# iqrfsim.net
KiCad netlist of a schematic drawn in EAGLE
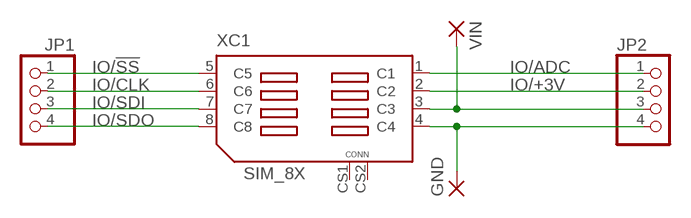
[diagram p0: schematic, sheet 1]

(export (version "E")
  (design (tool "Eeschema 10.0.6"))
  (components
    (comp (ref "GND")
      (value "1,6/0,9")
      (footprint "eagle-import:1,6_0,9")
      (libsource (lib "eagle-import") (part "1,6/0,9"))
    )
    (comp (ref "JP1")
      (value "PINHD-1X4")
      (footprint "eagle-import:1X04")
      (libsource (lib "eagle-import") (part "PINHD-1X4"))
    )
    (comp (ref "JP2")
      (value "PINHD-1X4")
      (footprint "eagle-import:1X04")
      (libsource (lib "eagle-import") (part "PINHD-1X4"))
    )
    (comp (ref "VIN")
      (value "1,6/0,9")
      (footprint "eagle-import:1,6_0,9")
      (libsource (lib "eagle-import") (part "1,6/0,9"))
    )
    (comp (ref "XC1")
      (value "SIM_8X")
      (footprint "eagle-import:SIM_8XPADS")
      (libsource (lib "eagle-import") (part "SIM_8X"))
    )
  )
  (nets
    (net (code "1") (name "/IO{slash}+3V") (class "Default")
      (node (ref "JP2") (pin "2") (pinfunction "2_2") (pintype "passive"))
      (node (ref "XC1") (pin "2") (pinfunction "C2_2") (pintype "passive"))
    )
    (net (code "2") (name "/IO{slash}ADC") (class "Default")
      (node (ref "JP2") (pin "1") (pinfunction "1_1") (pintype "passive"))
      (node (ref "XC1") (pin "1") (pinfunction "C1_1") (pintype "passive"))
    )
    (net (code "3") (name "/IO{slash}CLK") (class "Default")
      (node (ref "JP1") (pin "2") (pinfunction "2_2") (pintype "passive"))
      (node (ref "XC1") (pin "6") (pinfunction "C6_6") (pintype "passive"))
    )
    (net (code "4") (name "/IO{slash}SDI") (class "Default")
      (node (ref "JP1") (pin "3") (pinfunction "3_3") (pintype "passive"))
      (node (ref "XC1") (pin "7") (pinfunction "C7_7") (pintype "passive"))
    )
    (net (code "5") (name "/IO{slash}SDO") (class "Default")
      (node (ref "JP1") (pin "4") (pinfunction "4_4") (pintype "passive"))
      (node (ref "XC1") (pin "8") (pinfunction "C8_8") (pintype "passive"))
    )
    (net (code "6") (name "/IO{slash}~{SS}") (class "Default")
      (node (ref "JP1") (pin "1") (pinfunction "1_1") (pintype "passive"))
      (node (ref "XC1") (pin "5") (pinfunction "C5_5") (pintype "passive"))
    )
    (net (code "7") (name "Net-(GND-P)") (class "Default")
      (node (ref "GND") (pin "1") (pinfunction "P_1") (pintype "passive"))
      (node (ref "JP2") (pin "4") (pinfunction "4_4") (pintype "passive"))
      (node (ref "XC1") (pin "4") (pinfunction "C4_4") (pintype "passive"))
    )
    (net (code "8") (name "Net-(VIN-P)") (class "Default")
      (node (ref "JP2") (pin "3") (pinfunction "3_3") (pintype "passive"))
      (node (ref "VIN") (pin "1") (pinfunction "P_1") (pintype "passive"))
      (node (ref "XC1") (pin "3") (pinfunction "C3_3") (pintype "passive"))
    )
    (net (code "9") (name "unconnected-(XC1-P$1-PadCS1)") (class "Default")
      (node (ref "XC1") (pin "CS1") (pinfunction "P$1_CS1") (pintype "passive"))
    )
    (net (code "10") (name "unconnected-(XC1-P$2-PadCS2)") (class "Default")
      (node (ref "XC1") (pin "CS2") (pinfunction "P$2_CS2") (pintype "passive"))
    )
  )
)
